# core.net
KiCad netlist of a schematic drawn in EAGLE
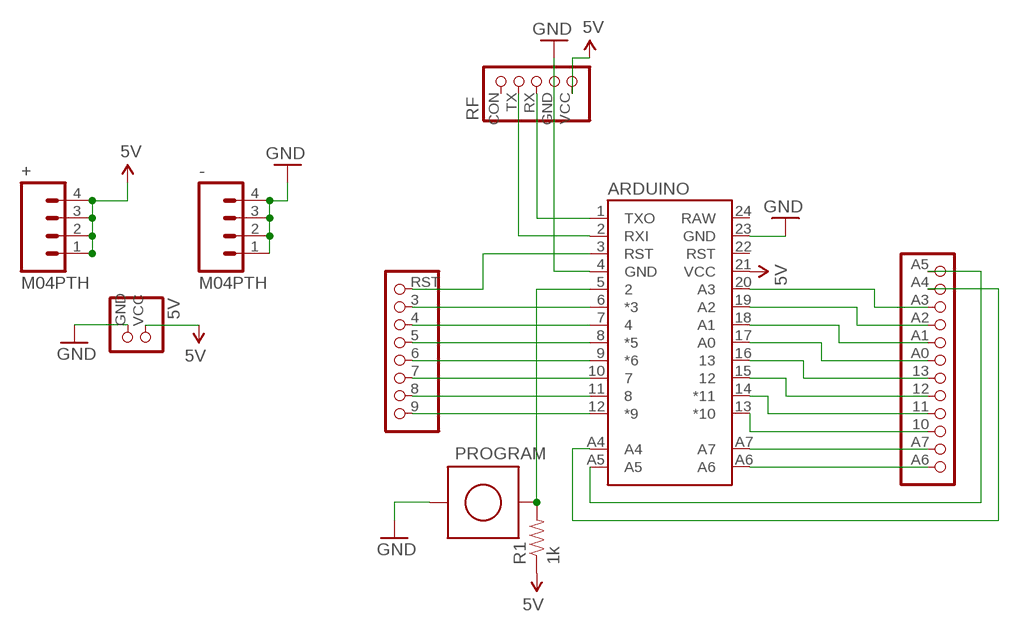
[diagram p0: schematic, sheet 1]

(export (version "E")
  (design (tool "Eeschema 10.0.6"))
  (components
    (comp (ref "+")
      (value "M04PTH")
      (footprint "eagle-import:1X04")
      (libsource (lib "eagle-import") (part "M04PTH"))
    )
    (comp (ref "-")
      (value "M04PTH")
      (footprint "eagle-import:1X04")
      (libsource (lib "eagle-import") (part "M04PTH"))
    )
    (comp (ref "5V")
      (value "DCPINHD-1X2")
      (footprint "eagle-import:1X02")
      (libsource (lib "eagle-import") (part "DCPINHD-1X2"))
    )
    (comp (ref "ARDUINO")
      (value "ARDUINO_PRO_MINI")
      (footprint "eagle-import:ARDUINO_PRO_MINI")
      (libsource (lib "eagle-import") (part "ARDUINO_PRO_MINI"))
    )
    (comp (ref "PROGRAM")
      (value "PUSHBUTTON")
      (footprint "eagle-import:PUSHBUTTON")
      (libsource (lib "eagle-import") (part "PUSHBUTTON"))
    )
    (comp (ref "R1")
      (value "1k")
      (footprint "eagle-import:AXIAL-0.1")
      (libsource (lib "eagle-import") (part "RESISTORPTH-1/4W-VERT"))
    )
    (comp (ref "RF")
      (value "RFPINHD-1X5")
      (footprint "eagle-import:1X05")
      (libsource (lib "eagle-import") (part "RFPINHD-1X5"))
    )
    (comp (ref "U$1")
      (value "RIGHTPINHD-1X12")
      (footprint "eagle-import:1X12")
      (libsource (lib "eagle-import") (part "RIGHTPINHD-1X12"))
    )
    (comp (ref "U$2")
      (value "LEFTPINHD-1X8")
      (footprint "eagle-import:1X08")
      (libsource (lib "eagle-import") (part "LEFTPINHD-1X8"))
    )
  )
  (nets
    (net (code "1") (name "5V") (class "Default")
      (node (ref "+") (pin "1") (pinfunction "1_1") (pintype "passive"))
      (node (ref "+") (pin "2") (pinfunction "2_2") (pintype "passive"))
      (node (ref "+") (pin "3") (pinfunction "3_3") (pintype "passive"))
      (node (ref "+") (pin "4") (pinfunction "4_4") (pintype "passive"))
      (node (ref "5V") (pin "VCC") (pinfunction "1_VCC") (pintype "passive"))
      (node (ref "ARDUINO") (pin "21") (pinfunction "VCC_21") (pintype "bidirectional"))
      (node (ref "R1") (pin "P$1") (pinfunction "1_P$1") (pintype "passive"))
      (node (ref "RF") (pin "VCC") (pinfunction "5_VCC") (pintype "passive"))
    )
    (net (code "2") (name "GND") (class "Default")
      (node (ref "-") (pin "1") (pinfunction "1_1") (pintype "passive"))
      (node (ref "-") (pin "2") (pinfunction "2_2") (pintype "passive"))
      (node (ref "-") (pin "3") (pinfunction "3_3") (pintype "passive"))
      (node (ref "-") (pin "4") (pinfunction "4_4") (pintype "passive"))
      (node (ref "5V") (pin "GND") (pinfunction "2_GND") (pintype "passive"))
      (node (ref "ARDUINO") (pin "23") (pinfunction "GND_23") (pintype "bidirectional"))
      (node (ref "ARDUINO") (pin "4") (pinfunction "GND_4") (pintype "bidirectional"))
      (node (ref "PROGRAM") (pin "P$1") (pinfunction "P$1_P$1") (pintype "input"))
      (node (ref "RF") (pin "GND") (pinfunction "4_GND") (pintype "passive"))
    )
    (net (code "3") (name "Net-(ARDUINO-*3)") (class "Default")
      (node (ref "ARDUINO") (pin "6") (pinfunction "*3_6") (pintype "bidirectional"))
      (node (ref "U$2") (pin "3") (pinfunction "7_3") (pintype "passive"))
    )
    (net (code "4") (name "Net-(ARDUINO-*5)") (class "Default")
      (node (ref "ARDUINO") (pin "8") (pinfunction "*5_8") (pintype "bidirectional"))
      (node (ref "U$2") (pin "5") (pinfunction "5_5") (pintype "passive"))
    )
    (net (code "5") (name "Net-(ARDUINO-*6)") (class "Default")
      (node (ref "ARDUINO") (pin "9") (pinfunction "*6_9") (pintype "bidirectional"))
      (node (ref "U$2") (pin "6") (pinfunction "4_6") (pintype "passive"))
    )
    (net (code "6") (name "Net-(ARDUINO-*9)") (class "Default")
      (node (ref "ARDUINO") (pin "12") (pinfunction "*9_12") (pintype "bidirectional"))
      (node (ref "U$2") (pin "9") (pinfunction "1_9") (pintype "passive"))
    )
    (net (code "7") (name "Net-(ARDUINO-*10)") (class "Default")
      (node (ref "ARDUINO") (pin "13") (pinfunction "*10_13") (pintype "bidirectional"))
      (node (ref "U$1") (pin "10") (pinfunction "3_10") (pintype "passive"))
    )
    (net (code "8") (name "Net-(ARDUINO-*11)") (class "Default")
      (node (ref "ARDUINO") (pin "14") (pinfunction "*11_14") (pintype "bidirectional"))
      (node (ref "U$1") (pin "11") (pinfunction "4_11") (pintype "passive"))
    )
    (net (code "9") (name "Net-(ARDUINO-2)") (class "Default")
      (node (ref "ARDUINO") (pin "5") (pinfunction "2_5") (pintype "bidirectional"))
      (node (ref "PROGRAM") (pin "P$2") (pinfunction "P$2_P$2") (pintype "output"))
      (node (ref "R1") (pin "P$2") (pinfunction "2_P$2") (pintype "passive"))
    )
    (net (code "10") (name "Net-(ARDUINO-4)") (class "Default")
      (node (ref "ARDUINO") (pin "7") (pinfunction "4_7") (pintype "bidirectional"))
      (node (ref "U$2") (pin "4") (pinfunction "6_4") (pintype "passive"))
    )
    (net (code "11") (name "Net-(ARDUINO-7)") (class "Default")
      (node (ref "ARDUINO") (pin "10") (pinfunction "7_10") (pintype "bidirectional"))
      (node (ref "U$2") (pin "7") (pinfunction "3_7") (pintype "passive"))
    )
    (net (code "12") (name "Net-(ARDUINO-8)") (class "Default")
      (node (ref "ARDUINO") (pin "11") (pinfunction "8_11") (pintype "bidirectional"))
      (node (ref "U$2") (pin "8") (pinfunction "2_8") (pintype "passive"))
    )
    (net (code "13") (name "Net-(ARDUINO-12)") (class "Default")
      (node (ref "ARDUINO") (pin "15") (pinfunction "12_15") (pintype "bidirectional"))
      (node (ref "U$1") (pin "12") (pinfunction "5_12") (pintype "passive"))
    )
    (net (code "14") (name "Net-(ARDUINO-13)") (class "Default")
      (node (ref "ARDUINO") (pin "16") (pinfunction "13_16") (pintype "bidirectional"))
      (node (ref "U$1") (pin "13") (pinfunction "6_13") (pintype "passive"))
    )
    (net (code "15") (name "Net-(ARDUINO-A0)") (class "Default")
      (node (ref "ARDUINO") (pin "17") (pinfunction "A0_17") (pintype "bidirectional"))
      (node (ref "U$1") (pin "A0") (pinfunction "7_A0") (pintype "passive"))
    )
    (net (code "16") (name "Net-(ARDUINO-A1)") (class "Default")
      (node (ref "ARDUINO") (pin "18") (pinfunction "A1_18") (pintype "bidirectional"))
      (node (ref "U$1") (pin "A1") (pinfunction "8_A1") (pintype "passive"))
    )
    (net (code "17") (name "Net-(ARDUINO-A2)") (class "Default")
      (node (ref "ARDUINO") (pin "19") (pinfunction "A2_19") (pintype "bidirectional"))
      (node (ref "U$1") (pin "A2") (pinfunction "9_A2") (pintype "passive"))
    )
    (net (code "18") (name "Net-(ARDUINO-A3)") (class "Default")
      (node (ref "ARDUINO") (pin "20") (pinfunction "A3_20") (pintype "bidirectional"))
      (node (ref "U$1") (pin "A3") (pinfunction "10_A3") (pintype "passive"))
    )
    (net (code "19") (name "Net-(ARDUINO-RXI)") (class "Default")
      (node (ref "ARDUINO") (pin "2") (pinfunction "RXI_2") (pintype "bidirectional"))
      (node (ref "RF") (pin "TX") (pinfunction "2_TX") (pintype "passive"))
    )
    (net (code "20") (name "Net-(ARDUINO-TXO)") (class "Default")
      (node (ref "ARDUINO") (pin "1") (pinfunction "TXO_1") (pintype "bidirectional"))
      (node (ref "RF") (pin "RX") (pinfunction "3_RX") (pintype "passive"))
    )
    (net (code "21") (name "Net-(U$1-1)") (class "Default")
      (node (ref "ARDUINO") (pin "A6") (pinfunction "A6_A6") (pintype "bidirectional"))
      (node (ref "U$1") (pin "A6") (pinfunction "1_A6") (pintype "passive"))
    )
    (net (code "22") (name "Net-(U$1-2)") (class "Default")
      (node (ref "ARDUINO") (pin "A7") (pinfunction "A7_A7") (pintype "bidirectional"))
      (node (ref "U$1") (pin "A7") (pinfunction "2_A7") (pintype "passive"))
    )
    (net (code "23") (name "Net-(U$1-11)") (class "Default")
      (node (ref "ARDUINO") (pin "A4") (pinfunction "A4_A4") (pintype "bidirectional"))
      (node (ref "U$1") (pin "A4") (pinfunction "11_A4") (pintype "passive"))
    )
    (net (code "24") (name "Net-(U$1-A7)") (class "Default")
      (node (ref "ARDUINO") (pin "A5") (pinfunction "A5_A5") (pintype "bidirectional"))
      (node (ref "U$1") (pin "A5") (pinfunction "A7_A5") (pintype "passive"))
    )
    (net (code "25") (name "Net-(U$2-8)") (class "Default")
      (node (ref "ARDUINO") (pin "3") (pinfunction "RST_3") (pintype "bidirectional"))
      (node (ref "U$2") (pin "RST") (pinfunction "8_RST") (pintype "passive"))
    )
    (net (code "26") (name "unconnected-(ARDUINO-RAW-Pad24)") (class "Default")
      (node (ref "ARDUINO") (pin "24") (pinfunction "RAW_24") (pintype "bidirectional"))
    )
    (net (code "27") (name "unconnected-(ARDUINO-RST-Pad22)") (class "Default")
      (node (ref "ARDUINO") (pin "22") (pinfunction "RST_22") (pintype "bidirectional"))
    )
    (net (code "28") (name "unconnected-(RF-1-PadCON)") (class "Default")
      (node (ref "RF") (pin "CON") (pinfunction "1_CON") (pintype "passive"))
    )
  )
)
